# COMANDO.net
KiCad netlist of a schematic drawn in Altium Designer
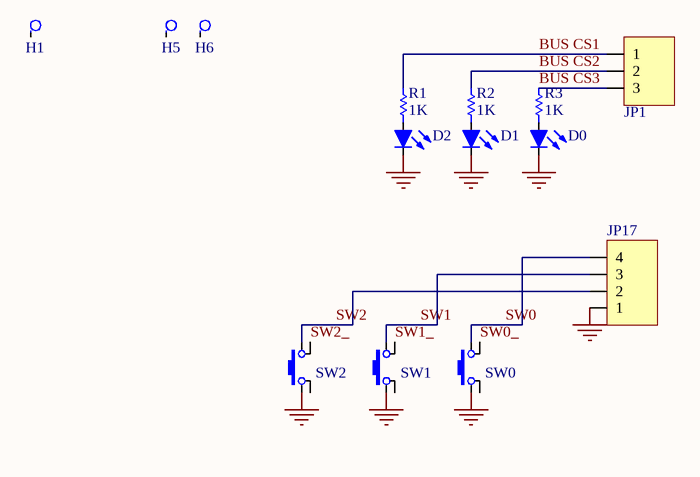
[diagram p0: COMANDO.SchDoc]

(export (version "E")
  (design (tool "Eeschema 10.0.6"))
  (components
    (comp (ref "D0")
      (value "Led 5mm Rojo Difuso")
      (footprint "LED5mm ROJO")
      (libsource (lib "FEDE") (part "Led 5mm Rojo Difuso"))
    )
    (comp (ref "D1")
      (value "Led 5mm Rojo Difuso")
      (footprint "LED5mm ROJO")
      (libsource (lib "FEDE") (part "Led 5mm Rojo Difuso"))
    )
    (comp (ref "D2")
      (value "Led 5mm Rojo Difuso")
      (footprint "LED5mm ROJO")
      (libsource (lib "FEDE") (part "Led 5mm Rojo Difuso"))
    )
    (comp (ref "H1")
      (value "Agujero de Montaje")
      (footprint "agujero")
      (libsource (lib "FEDE") (part "Agujero de Montaje"))
    )
    (comp (ref "H5")
      (value "Agujero de Montaje")
      (footprint "agujero")
      (libsource (lib "FEDE") (part "Agujero de Montaje"))
    )
    (comp (ref "H6")
      (value "Agujero de Montaje")
      (footprint "agujero")
      (libsource (lib "FEDE") (part "Agujero de Montaje"))
    )
    (comp (ref "JP1")
      (value "Header3x1")
      (footprint "CONPOL3X1_90")
      (description "Header 3x1")
      (libsource (lib "FEDE") (part "Header3x1"))
    )
    (comp (ref "JP17")
      (value "Header4x1")
      (footprint "CONPOL4x1_90")
      (description "Header 4x1")
      (libsource (lib "FEDE") (part "Header4x1"))
    )
    (comp (ref "R1")
      (value "1K")
      (footprint "1206NP")
      (description "Resistor")
      (fields (field (name "POWER") "0.25W") (field (name "Comment") "Res"))
      (libsource (lib "FEDE") (part "Res"))
    )
    (comp (ref "R2")
      (value "1K")
      (footprint "1206NP")
      (description "Resistor")
      (fields (field (name "POWER") "0.25W") (field (name "Comment") "Res"))
      (libsource (lib "FEDE") (part "Res"))
    )
    (comp (ref "R3")
      (value "1K")
      (footprint "1206NP")
      (description "Resistor")
      (fields (field (name "POWER") "0.25W") (field (name "Comment") "Res"))
      (libsource (lib "FEDE") (part "Res"))
    )
    (comp (ref "SW0") (value "SW_T_5MM") (footprint "SW_T_5MM") (libsource (lib "FEDE") (part "SW_T_5MM")))
    (comp (ref "SW1") (value "SW_T_5MM") (footprint "SW_T_5MM") (libsource (lib "FEDE") (part "SW_T_5MM")))
    (comp (ref "SW2") (value "SW_T_5MM") (footprint "SW_T_5MM") (libsource (lib "FEDE") (part "SW_T_5MM")))
  )
  (nets
    (net (code "1") (name "/BUS CS1") (class "Default")
      (node (ref "JP1") (pin "1") (pinfunction "1_1") (pintype "passive"))
      (node (ref "R1") (pin "2") (pinfunction "2_2") (pintype "passive"))
    )
    (net (code "2") (name "/BUS CS2") (class "Default")
      (node (ref "JP1") (pin "2") (pinfunction "2_2") (pintype "passive"))
      (node (ref "R2") (pin "2") (pinfunction "2_2") (pintype "passive"))
    )
    (net (code "3") (name "/BUS CS3") (class "Default")
      (node (ref "JP1") (pin "3") (pinfunction "3_3") (pintype "passive"))
      (node (ref "R3") (pin "2") (pinfunction "2_2") (pintype "passive"))
    )
    (net (code "4") (name "/SW0") (class "Default")
      (node (ref "JP17") (pin "4") (pinfunction "4_4") (pintype "passive"))
      (node (ref "SW0") (pin "4") (pinfunction "4_4") (pintype "passive"))
    )
    (net (code "5") (name "/SW0_") (class "Default")
      (node (ref "SW0") (pin "2") (pinfunction "2_2") (pintype "passive"))
    )
    (net (code "6") (name "/SW1") (class "Default")
      (node (ref "JP17") (pin "3") (pinfunction "3_3") (pintype "passive"))
      (node (ref "SW1") (pin "4") (pinfunction "4_4") (pintype "passive"))
    )
    (net (code "7") (name "/SW1_") (class "Default")
      (node (ref "SW1") (pin "2") (pinfunction "2_2") (pintype "passive"))
    )
    (net (code "8") (name "/SW2") (class "Default")
      (node (ref "JP17") (pin "2") (pinfunction "2_2") (pintype "passive"))
      (node (ref "SW2") (pin "4") (pinfunction "4_4") (pintype "passive"))
    )
    (net (code "9") (name "/SW2_") (class "Default")
      (node (ref "SW2") (pin "2") (pinfunction "2_2") (pintype "passive"))
    )
    (net (code "10") (name "GND") (class "Default")
      (node (ref "D0") (pin "2") (pinfunction "K_2") (pintype "passive"))
      (node (ref "D1") (pin "2") (pinfunction "K_2") (pintype "passive"))
      (node (ref "D2") (pin "2") (pinfunction "K_2") (pintype "passive"))
      (node (ref "JP17") (pin "1") (pinfunction "1_1") (pintype "passive"))
      (node (ref "SW0") (pin "3") (pinfunction "3_3") (pintype "passive"))
      (node (ref "SW1") (pin "3") (pinfunction "3_3") (pintype "passive"))
      (node (ref "SW2") (pin "3") (pinfunction "3_3") (pintype "passive"))
    )
    (net (code "11") (name "Net-(D0-A)") (class "Default")
      (node (ref "D0") (pin "1") (pinfunction "A_1") (pintype "passive"))
      (node (ref "R3") (pin "1") (pinfunction "1_1") (pintype "passive"))
    )
    (net (code "12") (name "Net-(D1-A)") (class "Default")
      (node (ref "D1") (pin "1") (pinfunction "A_1") (pintype "passive"))
      (node (ref "R2") (pin "1") (pinfunction "1_1") (pintype "passive"))
    )
    (net (code "13") (name "Net-(D2-A)") (class "Default")
      (node (ref "D2") (pin "1") (pinfunction "A_1") (pintype "passive"))
      (node (ref "R1") (pin "1") (pinfunction "1_1") (pintype "passive"))
    )
    (net (code "14") (name "unconnected-(H1-Pad1)") (class "Default")
      (node (ref "H1") (pin "1") (pinfunction "1_1") (pintype "passive"))
    )
    (net (code "15") (name "unconnected-(H5-Pad1)") (class "Default")
      (node (ref "H5") (pin "1") (pinfunction "1_1") (pintype "passive"))
    )
    (net (code "16") (name "unconnected-(H6-Pad1)") (class "Default")
      (node (ref "H6") (pin "1") (pinfunction "1_1") (pintype "passive"))
    )
    (net (code "17") (name "unconnected-(SW0-Pad1)") (class "Default")
      (node (ref "SW0") (pin "1") (pinfunction "1_1") (pintype "passive"))
    )
    (net (code "18") (name "unconnected-(SW1-Pad1)") (class "Default")
      (node (ref "SW1") (pin "1") (pinfunction "1_1") (pintype "passive"))
    )
    (net (code "19") (name "unconnected-(SW2-Pad1)") (class "Default")
      (node (ref "SW2") (pin "1") (pinfunction "1_1") (pintype "passive"))
    )
  )
)
